# STM32F050F_Base.net
KiCad netlist of a schematic drawn in EAGLE
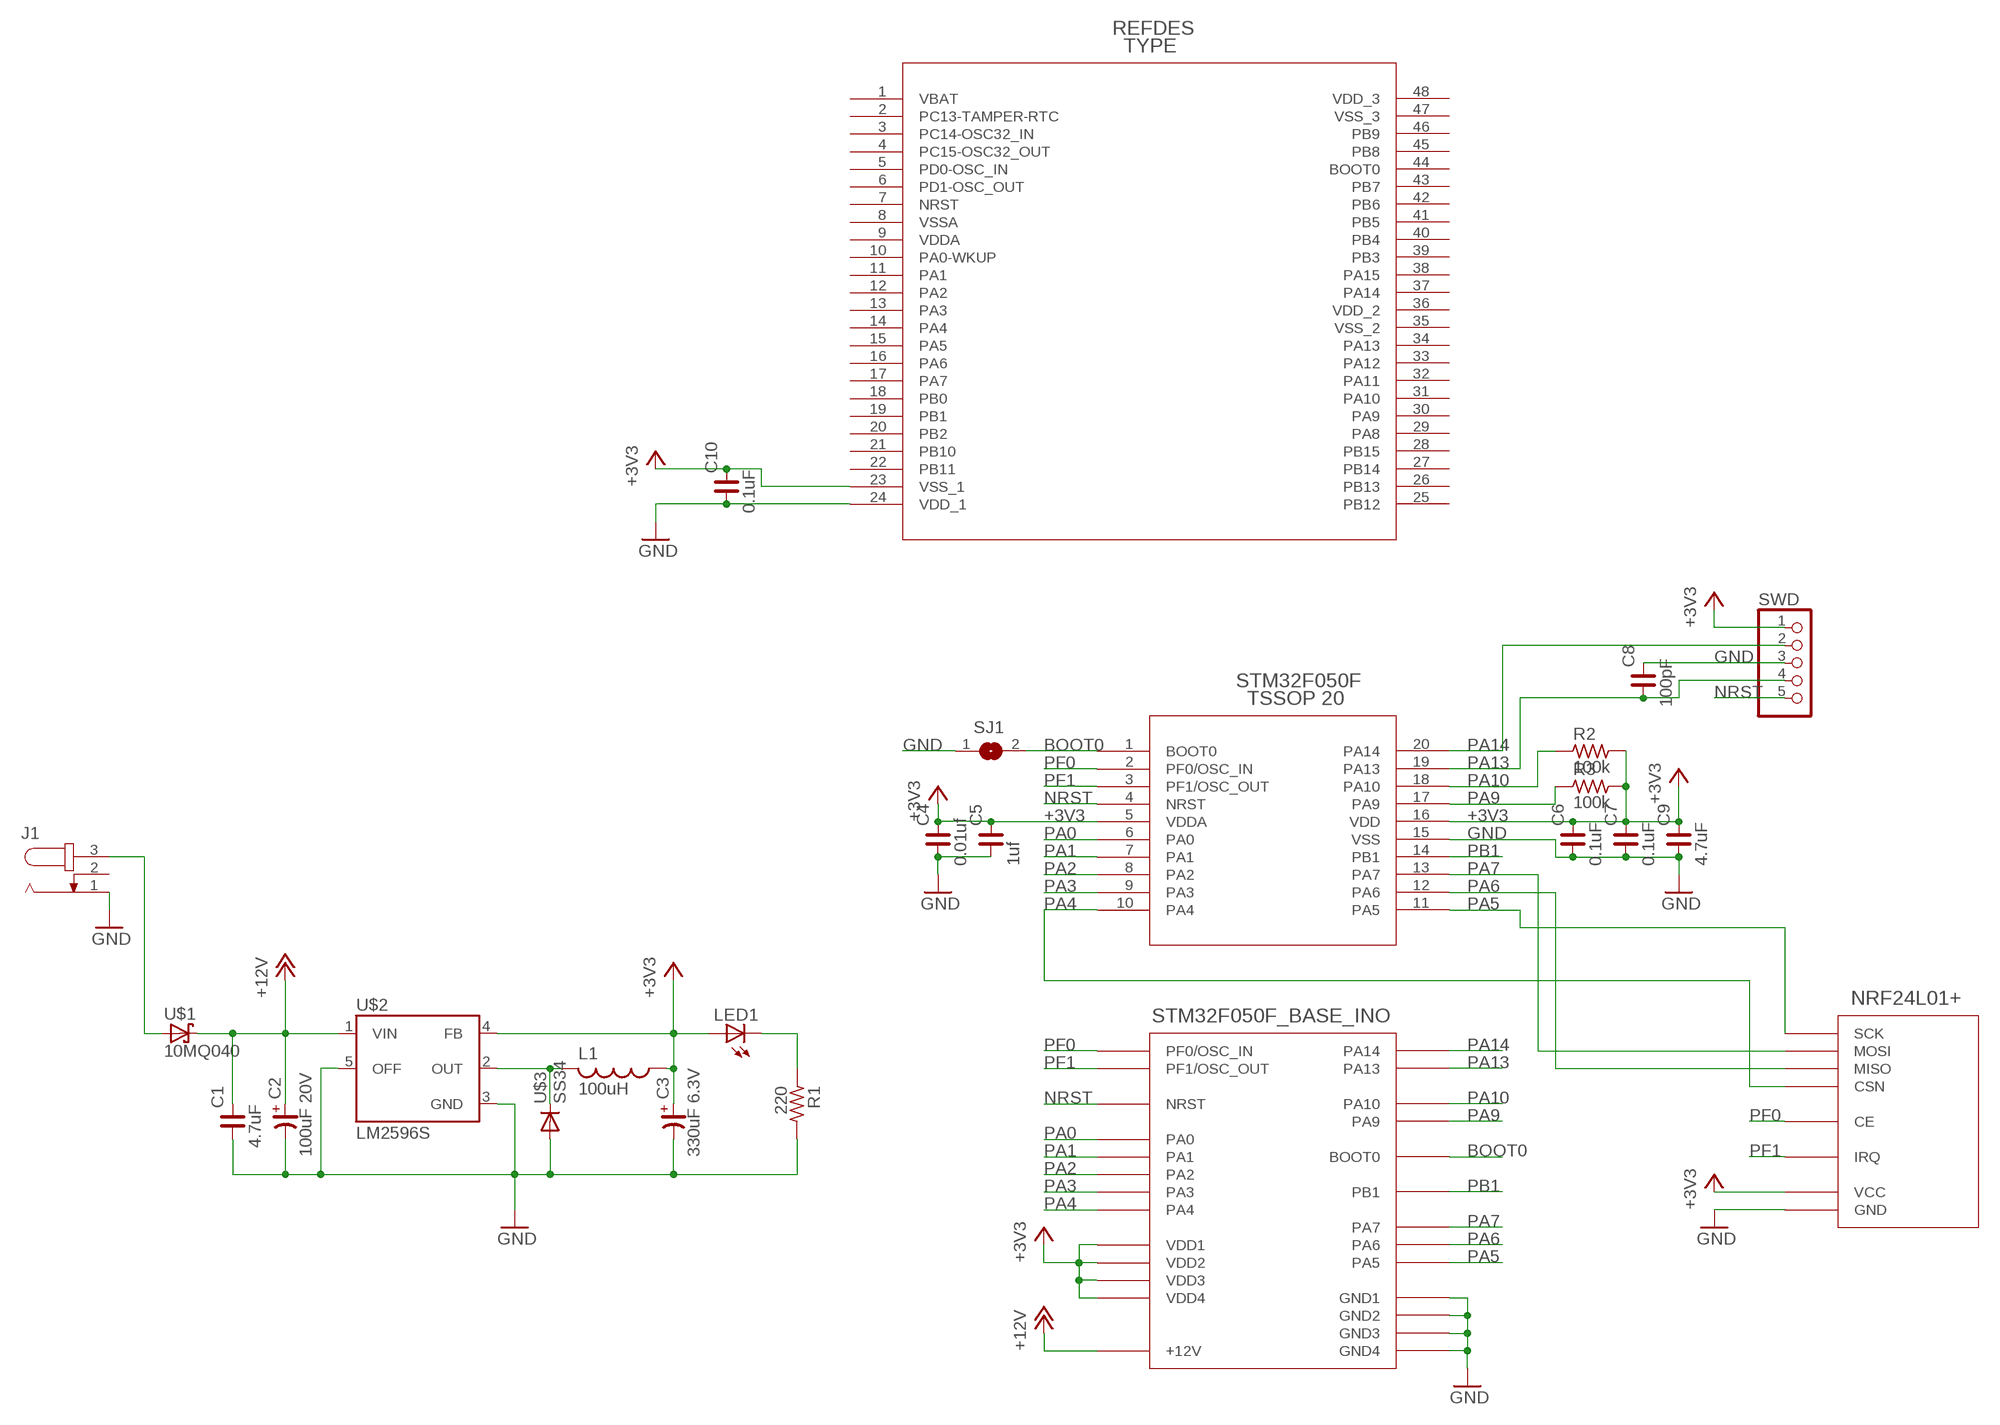
[diagram p0: schematic, sheet 1]

(export (version "E")
  (design (tool "Eeschema 10.0.6"))
  (components
    (comp (ref "C1")
      (value "4.7uF")
      (footprint "eagle-import:C1206")
      (libsource (lib "eagle-import") (part "C_1206"))
    )
    (comp (ref "C2")
      (value "100uF 20V")
      (footprint "eagle-import:C7343_T")
      (libsource (lib "eagle-import") (part "CP_7343"))
    )
    (comp (ref "C3")
      (value "330uF 6.3V")
      (footprint "eagle-import:C7343_T")
      (libsource (lib "eagle-import") (part "CP_7343"))
    )
    (comp (ref "C4")
      (value "0.01uf")
      (footprint "eagle-import:C1206")
      (libsource (lib "eagle-import") (part "C_1206"))
    )
    (comp (ref "C5")
      (value "1uf")
      (footprint "eagle-import:C1206")
      (libsource (lib "eagle-import") (part "C_1206"))
    )
    (comp (ref "C6")
      (value "0.1uF")
      (footprint "eagle-import:C1206")
      (libsource (lib "eagle-import") (part "C_1206"))
    )
    (comp (ref "C7")
      (value "0.1uF")
      (footprint "eagle-import:C1206")
      (libsource (lib "eagle-import") (part "C_1206"))
    )
    (comp (ref "C8")
      (value "100pF")
      (footprint "eagle-import:C1206")
      (libsource (lib "eagle-import") (part "C_1206"))
    )
    (comp (ref "C9")
      (value "4.7uF")
      (footprint "eagle-import:C1206")
      (libsource (lib "eagle-import") (part "C_1206"))
    )
    (comp (ref "C10")
      (value "0.1uF")
      (footprint "eagle-import:C1206")
      (libsource (lib "eagle-import") (part "C_1206"))
    )
    (comp (ref "J1")
      (value "JACK-PLUG0")
      (footprint "eagle-import:SPC4077")
      (libsource (lib "eagle-import") (part "JACK-PLUG0"))
    )
    (comp (ref "L1")
      (value "100uH")
      (footprint "eagle-import:POWER-CHOKE_WE-TPC")
      (libsource (lib "eagle-import") (part "L-USWE-TPC"))
    )
    (comp (ref "LED1")
      (value "LEDCHIPLED_1206")
      (footprint "eagle-import:CHIPLED_1206")
      (libsource (lib "eagle-import") (part "LEDCHIPLED_1206"))
    )
    (comp (ref "R1")
      (value "220")
      (footprint "eagle-import:R1206")
      (libsource (lib "eagle-import") (part "R_1206"))
    )
    (comp (ref "R2")
      (value "100k")
      (footprint "eagle-import:R1206")
      (libsource (lib "eagle-import") (part "R_1206"))
    )
    (comp (ref "R3")
      (value "100k")
      (footprint "eagle-import:R1206")
      (libsource (lib "eagle-import") (part "R_1206"))
    )
    (comp (ref "SJ1") (value "SJ") (footprint "eagle-import:SJ") (libsource (lib "eagle-import") (part "SJ")))
    (comp (ref "SWD")
      (value "PINHD-1X05_2.54-90°-S")
      (footprint "eagle-import:1X05_90-S")
      (libsource (lib "eagle-import") (part "PINHD-1X05_2.54-90°-S"))
    )
    (comp (ref "U$1")
      (value "10MQ040")
      (footprint "eagle-import:SMA")
      (libsource (lib "eagle-import") (part "10MQ040"))
    )
    (comp (ref "U$2")
      (value "LM2596S")
      (footprint "eagle-import:TO263-5")
      (libsource (lib "eagle-import") (part "LM2596S"))
    )
    (comp (ref "U$3")
      (value "SS34")
      (footprint "eagle-import:SMC")
      (libsource (lib "eagle-import") (part "DIODE-SMC"))
    )
    (comp (ref "U$4")
      (value "STM32F050F4P6")
      (footprint "eagle-import:TSSOP20")
      (libsource (lib "eagle-import") (part "STM32F050F4P6"))
    )
    (comp (ref "U$5")
      (value "STM32F050F_BASE_INO")
      (footprint "eagle-import:STM32_BASE_INO")
      (libsource (lib "eagle-import") (part "STM32F050F_BASE_INO"))
    )
    (comp (ref "U$6")
      (value "NRF24L01+")
      (footprint "eagle-import:NRF24L01+")
      (libsource (lib "eagle-import") (part "NRF24L01+"))
    )
    (comp (ref "U$7")
      (value "STM32F100C8T6B")
      (footprint "eagle-import:LQFP-48")
      (libsource (lib "eagle-import") (part "STM32F100C8T6B"))
    )
  )
  (nets
    (net (code "1") (name "+3V3") (class "Default")
      (node (ref "C10") (pin "2") (pinfunction "2_2") (pintype "passive"))
      (node (ref "C3") (pin "+") (pinfunction "+_+") (pintype "passive"))
      (node (ref "C4") (pin "2") (pinfunction "2_2") (pintype "passive"))
      (node (ref "C5") (pin "2") (pinfunction "2_2") (pintype "passive"))
      (node (ref "C6") (pin "2") (pinfunction "2_2") (pintype "passive"))
      (node (ref "C7") (pin "2") (pinfunction "2_2") (pintype "passive"))
      (node (ref "C9") (pin "2") (pinfunction "2_2") (pintype "passive"))
      (node (ref "L1") (pin "1") (pinfunction "1_1") (pintype "passive"))
      (node (ref "LED1") (pin "A") (pinfunction "A_A") (pintype "passive"))
      (node (ref "R2") (pin "2") (pinfunction "2_2") (pintype "passive"))
      (node (ref "R3") (pin "2") (pinfunction "2_2") (pintype "passive"))
      (node (ref "SWD") (pin "1") (pinfunction "1_1") (pintype "passive"))
      (node (ref "U$2") (pin "4") (pinfunction "FB_4") (pintype "input"))
      (node (ref "U$4") (pin "16") (pinfunction "VDD_16") (pintype "passive"))
      (node (ref "U$4") (pin "5") (pinfunction "VDDA_5") (pintype "passive"))
      (node (ref "U$5") (pin "VDD1") (pinfunction "VDD1_VDD1") (pintype "passive"))
      (node (ref "U$5") (pin "VDD2") (pinfunction "VDD2_VDD2") (pintype "passive"))
      (node (ref "U$5") (pin "VDD3") (pinfunction "VDD3_VDD3") (pintype "passive"))
      (node (ref "U$5") (pin "VDD4") (pinfunction "VDD4_VDD4") (pintype "passive"))
      (node (ref "U$6") (pin "VCC") (pinfunction "VCC_VCC") (pintype "passive"))
      (node (ref "U$7") (pin "23") (pinfunction "VSS_1_23") (pintype "passive"))
    )
    (net (code "2") (name "+12V") (class "Default")
      (node (ref "C1") (pin "2") (pinfunction "2_2") (pintype "passive"))
      (node (ref "C2") (pin "+") (pinfunction "+_+") (pintype "passive"))
      (node (ref "U$1") (pin "C") (pinfunction "C_C") (pintype "passive"))
      (node (ref "U$2") (pin "1") (pinfunction "VIN_1") (pintype "power_in"))
      (node (ref "U$5") (pin "+12V") (pinfunction "+12V_+12V") (pintype "passive"))
    )
    (net (code "3") (name "/BOOT0") (class "Default")
      (node (ref "SJ1") (pin "2") (pinfunction "2_2") (pintype "passive"))
      (node (ref "U$4") (pin "1") (pinfunction "BOOT0_1") (pintype "passive"))
      (node (ref "U$5") (pin "BOOT0") (pinfunction "BOOT0_BOOT0") (pintype "passive"))
    )
    (net (code "4") (name "/NRST") (class "Default")
      (node (ref "SWD") (pin "5") (pinfunction "5_5") (pintype "passive"))
      (node (ref "U$4") (pin "4") (pinfunction "NRST_4") (pintype "passive"))
      (node (ref "U$5") (pin "NRST") (pinfunction "NRST_NRST") (pintype "passive"))
    )
    (net (code "5") (name "/PA0") (class "Default")
      (node (ref "U$4") (pin "6") (pinfunction "PA0_6") (pintype "passive"))
      (node (ref "U$5") (pin "PA0") (pinfunction "PA0_PA0") (pintype "passive"))
    )
    (net (code "6") (name "/PA1") (class "Default")
      (node (ref "U$4") (pin "7") (pinfunction "PA1_7") (pintype "passive"))
      (node (ref "U$5") (pin "PA1") (pinfunction "PA1_PA1") (pintype "passive"))
    )
    (net (code "7") (name "/PA2") (class "Default")
      (node (ref "U$4") (pin "8") (pinfunction "PA2_8") (pintype "passive"))
      (node (ref "U$5") (pin "PA2") (pinfunction "PA2_PA2") (pintype "passive"))
    )
    (net (code "8") (name "/PA3") (class "Default")
      (node (ref "U$4") (pin "9") (pinfunction "PA3_9") (pintype "passive"))
      (node (ref "U$5") (pin "PA3") (pinfunction "PA3_PA3") (pintype "passive"))
    )
    (net (code "9") (name "/PA4") (class "Default")
      (node (ref "U$4") (pin "10") (pinfunction "PA4_10") (pintype "passive"))
      (node (ref "U$5") (pin "PA4") (pinfunction "PA4_PA4") (pintype "passive"))
      (node (ref "U$6") (pin "CSN") (pinfunction "CSN_CSN") (pintype "passive"))
    )
    (net (code "10") (name "/PA5") (class "Default")
      (node (ref "U$4") (pin "11") (pinfunction "PA5_11") (pintype "passive"))
      (node (ref "U$5") (pin "PA5") (pinfunction "PA5_PA5") (pintype "passive"))
      (node (ref "U$6") (pin "SCK") (pinfunction "SCK_SCK") (pintype "passive"))
    )
    (net (code "11") (name "/PA6") (class "Default")
      (node (ref "U$4") (pin "12") (pinfunction "PA6_12") (pintype "passive"))
      (node (ref "U$5") (pin "PA6") (pinfunction "PA6_PA6") (pintype "passive"))
      (node (ref "U$6") (pin "MISO") (pinfunction "MISO_MISO") (pintype "passive"))
    )
    (net (code "12") (name "/PA7") (class "Default")
      (node (ref "U$4") (pin "13") (pinfunction "PA7_13") (pintype "passive"))
      (node (ref "U$5") (pin "PA7") (pinfunction "PA7_PA7") (pintype "passive"))
      (node (ref "U$6") (pin "MOSI") (pinfunction "MOSI_MOSI") (pintype "passive"))
    )
    (net (code "13") (name "/PA9") (class "Default")
      (node (ref "R3") (pin "1") (pinfunction "1_1") (pintype "passive"))
      (node (ref "U$4") (pin "17") (pinfunction "PA9_17") (pintype "passive"))
      (node (ref "U$5") (pin "PA9") (pinfunction "PA9_PA9") (pintype "passive"))
    )
    (net (code "14") (name "/PA10") (class "Default")
      (node (ref "R2") (pin "1") (pinfunction "1_1") (pintype "passive"))
      (node (ref "U$4") (pin "18") (pinfunction "PA10_18") (pintype "passive"))
      (node (ref "U$5") (pin "PA10") (pinfunction "PA10_PA10") (pintype "passive"))
    )
    (net (code "15") (name "/PA13") (class "Default")
      (node (ref "C8") (pin "1") (pinfunction "1_1") (pintype "passive"))
      (node (ref "SWD") (pin "4") (pinfunction "4_4") (pintype "passive"))
      (node (ref "U$4") (pin "19") (pinfunction "PA13_19") (pintype "passive"))
      (node (ref "U$5") (pin "PA13") (pinfunction "PA13_PA13") (pintype "passive"))
    )
    (net (code "16") (name "/PA14") (class "Default")
      (node (ref "SWD") (pin "2") (pinfunction "2_2") (pintype "passive"))
      (node (ref "U$4") (pin "20") (pinfunction "PA14_20") (pintype "passive"))
      (node (ref "U$5") (pin "PA14") (pinfunction "PA14_PA14") (pintype "passive"))
    )
    (net (code "17") (name "/PB1") (class "Default")
      (node (ref "U$4") (pin "14") (pinfunction "PB1_14") (pintype "passive"))
      (node (ref "U$5") (pin "PB1") (pinfunction "PB1_PB1") (pintype "passive"))
    )
    (net (code "18") (name "/PF0") (class "Default")
      (node (ref "U$4") (pin "2") (pinfunction "PF0/OSC_IN_2") (pintype "passive"))
      (node (ref "U$5") (pin "PF0") (pinfunction "PF0/OSC_IN_PF0") (pintype "passive"))
      (node (ref "U$6") (pin "CE") (pinfunction "CE_CE") (pintype "passive"))
    )
    (net (code "19") (name "/PF1") (class "Default")
      (node (ref "U$4") (pin "3") (pinfunction "PF1/OSC_OUT_3") (pintype "passive"))
      (node (ref "U$5") (pin "PF1") (pinfunction "PF1/OSC_OUT_PF1") (pintype "passive"))
      (node (ref "U$6") (pin "IRQ") (pinfunction "IRQ_IRQ") (pintype "passive"))
    )
    (net (code "20") (name "GND") (class "Default")
      (node (ref "C1") (pin "1") (pinfunction "1_1") (pintype "passive"))
      (node (ref "C10") (pin "1") (pinfunction "1_1") (pintype "passive"))
      (node (ref "C2") (pin "-") (pinfunction "-_-") (pintype "passive"))
      (node (ref "C3") (pin "-") (pinfunction "-_-") (pintype "passive"))
      (node (ref "C4") (pin "1") (pinfunction "1_1") (pintype "passive"))
      (node (ref "C5") (pin "1") (pinfunction "1_1") (pintype "passive"))
      (node (ref "C6") (pin "1") (pinfunction "1_1") (pintype "passive"))
      (node (ref "C7") (pin "1") (pinfunction "1_1") (pintype "passive"))
      (node (ref "C8") (pin "2") (pinfunction "2_2") (pintype "passive"))
      (node (ref "C9") (pin "1") (pinfunction "1_1") (pintype "passive"))
      (node (ref "J1") (pin "1") (pinfunction "1_1") (pintype "passive"))
      (node (ref "R1") (pin "2") (pinfunction "2_2") (pintype "passive"))
      (node (ref "SJ1") (pin "1") (pinfunction "1_1") (pintype "passive"))
      (node (ref "SWD") (pin "3") (pinfunction "3_3") (pintype "passive"))
      (node (ref "U$2") (pin "3") (pinfunction "GND_3") (pintype "power_in"))
      (node (ref "U$2") (pin "5") (pinfunction "OFF_5") (pintype "input"))
      (node (ref "U$3") (pin "A") (pinfunction "A_A") (pintype "passive"))
      (node (ref "U$4") (pin "15") (pinfunction "VSS_15") (pintype "passive"))
      (node (ref "U$5") (pin "GND1") (pinfunction "GND1_GND1") (pintype "passive"))
      (node (ref "U$5") (pin "GND2") (pinfunction "GND2_GND2") (pintype "passive"))
      (node (ref "U$5") (pin "GND3") (pinfunction "GND3_GND3") (pintype "passive"))
      (node (ref "U$5") (pin "GND4") (pinfunction "GND4_GND4") (pintype "passive"))
      (node (ref "U$6") (pin "GND") (pinfunction "GND_GND") (pintype "passive"))
      (node (ref "U$7") (pin "24") (pinfunction "VDD_1_24") (pintype "passive"))
    )
    (net (code "21") (name "Net-(J1-Pad3)") (class "Default")
      (node (ref "J1") (pin "3") (pinfunction "3_3") (pintype "passive"))
      (node (ref "U$1") (pin "A") (pinfunction "A_A") (pintype "passive"))
    )
    (net (code "22") (name "Net-(LED1-PadC)") (class "Default")
      (node (ref "LED1") (pin "C") (pinfunction "C_C") (pintype "passive"))
      (node (ref "R1") (pin "1") (pinfunction "1_1") (pintype "passive"))
    )
    (net (code "23") (name "Net-(U$2-OUT)") (class "Default")
      (node (ref "L1") (pin "2") (pinfunction "2_2") (pintype "passive"))
      (node (ref "U$2") (pin "2") (pinfunction "OUT_2") (pintype "output"))
      (node (ref "U$3") (pin "C") (pinfunction "C_C") (pintype "passive"))
    )
    (net (code "24") (name "unconnected-(J1-Pad2)") (class "Default")
      (node (ref "J1") (pin "2") (pinfunction "2_2") (pintype "passive"))
    )
    (net (code "25") (name "unconnected-(U$7-BOOT0-Pad44)") (class "Default")
      (node (ref "U$7") (pin "44") (pinfunction "BOOT0_44") (pintype "passive"))
    )
    (net (code "26") (name "unconnected-(U$7-NRST-Pad7)") (class "Default")
      (node (ref "U$7") (pin "7") (pinfunction "NRST_7") (pintype "passive"))
    )
    (net (code "27") (name "unconnected-(U$7-PA0-WKUP-Pad10)") (class "Default")
      (node (ref "U$7") (pin "10") (pinfunction "PA0-WKUP_10") (pintype "passive"))
    )
    (net (code "28") (name "unconnected-(U$7-PA1-Pad11)") (class "Default")
      (node (ref "U$7") (pin "11") (pinfunction "PA1_11") (pintype "passive"))
    )
    (net (code "29") (name "unconnected-(U$7-PA2-Pad12)") (class "Default")
      (node (ref "U$7") (pin "12") (pinfunction "PA2_12") (pintype "passive"))
    )
    (net (code "30") (name "unconnected-(U$7-PA3-Pad13)") (class "Default")
      (node (ref "U$7") (pin "13") (pinfunction "PA3_13") (pintype "passive"))
    )
    (net (code "31") (name "unconnected-(U$7-PA4-Pad14)") (class "Default")
      (node (ref "U$7") (pin "14") (pinfunction "PA4_14") (pintype "passive"))
    )
    (net (code "32") (name "unconnected-(U$7-PA5-Pad15)") (class "Default")
      (node (ref "U$7") (pin "15") (pinfunction "PA5_15") (pintype "passive"))
    )
    (net (code "33") (name "unconnected-(U$7-PA6-Pad16)") (class "Default")
      (node (ref "U$7") (pin "16") (pinfunction "PA6_16") (pintype "passive"))
    )
    (net (code "34") (name "unconnected-(U$7-PA7-Pad17)") (class "Default")
      (node (ref "U$7") (pin "17") (pinfunction "PA7_17") (pintype "passive"))
    )
    (net (code "35") (name "unconnected-(U$7-PA8-Pad29)") (class "Default")
      (node (ref "U$7") (pin "29") (pinfunction "PA8_29") (pintype "passive"))
    )
    (net (code "36") (name "unconnected-(U$7-PA9-Pad30)") (class "Default")
      (node (ref "U$7") (pin "30") (pinfunction "PA9_30") (pintype "passive"))
    )
    (net (code "37") (name "unconnected-(U$7-PA10-Pad31)") (class "Default")
      (node (ref "U$7") (pin "31") (pinfunction "PA10_31") (pintype "passive"))
    )
    (net (code "38") (name "unconnected-(U$7-PA11-Pad32)") (class "Default")
      (node (ref "U$7") (pin "32") (pinfunction "PA11_32") (pintype "passive"))
    )
    (net (code "39") (name "unconnected-(U$7-PA12-Pad33)") (class "Default")
      (node (ref "U$7") (pin "33") (pinfunction "PA12_33") (pintype "passive"))
    )
    (net (code "40") (name "unconnected-(U$7-PA13-Pad34)") (class "Default")
      (node (ref "U$7") (pin "34") (pinfunction "PA13_34") (pintype "passive"))
    )
    (net (code "41") (name "unconnected-(U$7-PA14-Pad37)") (class "Default")
      (node (ref "U$7") (pin "37") (pinfunction "PA14_37") (pintype "passive"))
    )
    (net (code "42") (name "unconnected-(U$7-PA15-Pad38)") (class "Default")
      (node (ref "U$7") (pin "38") (pinfunction "PA15_38") (pintype "passive"))
    )
    (net (code "43") (name "unconnected-(U$7-PB0-Pad18)") (class "Default")
      (node (ref "U$7") (pin "18") (pinfunction "PB0_18") (pintype "passive"))
    )
    (net (code "44") (name "unconnected-(U$7-PB1-Pad19)") (class "Default")
      (node (ref "U$7") (pin "19") (pinfunction "PB1_19") (pintype "passive"))
    )
    (net (code "45") (name "unconnected-(U$7-PB2-Pad20)") (class "Default")
      (node (ref "U$7") (pin "20") (pinfunction "PB2_20") (pintype "passive"))
    )
    (net (code "46") (name "unconnected-(U$7-PB3-Pad39)") (class "Default")
      (node (ref "U$7") (pin "39") (pinfunction "PB3_39") (pintype "passive"))
    )
    (net (code "47") (name "unconnected-(U$7-PB4-Pad40)") (class "Default")
      (node (ref "U$7") (pin "40") (pinfunction "PB4_40") (pintype "passive"))
    )
    (net (code "48") (name "unconnected-(U$7-PB5-Pad41)") (class "Default")
      (node (ref "U$7") (pin "41") (pinfunction "PB5_41") (pintype "passive"))
    )
    (net (code "49") (name "unconnected-(U$7-PB6-Pad42)") (class "Default")
      (node (ref "U$7") (pin "42") (pinfunction "PB6_42") (pintype "passive"))
    )
    (net (code "50") (name "unconnected-(U$7-PB7-Pad43)") (class "Default")
      (node (ref "U$7") (pin "43") (pinfunction "PB7_43") (pintype "passive"))
    )
    (net (code "51") (name "unconnected-(U$7-PB8-Pad45)") (class "Default")
      (node (ref "U$7") (pin "45") (pinfunction "PB8_45") (pintype "passive"))
    )
    (net (code "52") (name "unconnected-(U$7-PB9-Pad46)") (class "Default")
      (node (ref "U$7") (pin "46") (pinfunction "PB9_46") (pintype "passive"))
    )
    (net (code "53") (name "unconnected-(U$7-PB10-Pad21)") (class "Default")
      (node (ref "U$7") (pin "21") (pinfunction "PB10_21") (pintype "passive"))
    )
    (net (code "54") (name "unconnected-(U$7-PB11-Pad22)") (class "Default")
      (node (ref "U$7") (pin "22") (pinfunction "PB11_22") (pintype "passive"))
    )
    (net (code "55") (name "unconnected-(U$7-PB12-Pad25)") (class "Default")
      (node (ref "U$7") (pin "25") (pinfunction "PB12_25") (pintype "passive"))
    )
    (net (code "56") (name "unconnected-(U$7-PB13-Pad26)") (class "Default")
      (node (ref "U$7") (pin "26") (pinfunction "PB13_26") (pintype "passive"))
    )
    (net (code "57") (name "unconnected-(U$7-PB14-Pad27)") (class "Default")
      (node (ref "U$7") (pin "27") (pinfunction "PB14_27") (pintype "passive"))
    )
    (net (code "58") (name "unconnected-(U$7-PB15-Pad28)") (class "Default")
      (node (ref "U$7") (pin "28") (pinfunction "PB15_28") (pintype "passive"))
    )
    (net (code "59") (name "unconnected-(U$7-PC13-TAMPER-RTC-Pad2)") (class "Default")
      (node (ref "U$7") (pin "2") (pinfunction "PC13-TAMPER-RTC_2") (pintype "passive"))
    )
    (net (code "60") (name "unconnected-(U$7-PC14-OSC32_IN-Pad3)") (class "Default")
      (node (ref "U$7") (pin "3") (pinfunction "PC14-OSC32_IN_3") (pintype "passive"))
    )
    (net (code "61") (name "unconnected-(U$7-PC15-OSC32_OUT-Pad4)") (class "Default")
      (node (ref "U$7") (pin "4") (pinfunction "PC15-OSC32_OUT_4") (pintype "passive"))
    )
    (net (code "62") (name "unconnected-(U$7-PD0-OSC_IN-Pad5)") (class "Default")
      (node (ref "U$7") (pin "5") (pinfunction "PD0-OSC_IN_5") (pintype "passive"))
    )
    (net (code "63") (name "unconnected-(U$7-PD1-OSC_OUT-Pad6)") (class "Default")
      (node (ref "U$7") (pin "6") (pinfunction "PD1-OSC_OUT_6") (pintype "passive"))
    )
    (net (code "64") (name "unconnected-(U$7-VBAT-Pad1)") (class "Default")
      (node (ref "U$7") (pin "1") (pinfunction "VBAT_1") (pintype "passive"))
    )
    (net (code "65") (name "unconnected-(U$7-VDDA-Pad9)") (class "Default")
      (node (ref "U$7") (pin "9") (pinfunction "VDDA_9") (pintype "passive"))
    )
    (net (code "66") (name "unconnected-(U$7-VDD_2-Pad36)") (class "Default")
      (node (ref "U$7") (pin "36") (pinfunction "VDD_2_36") (pintype "passive"))
    )
    (net (code "67") (name "unconnected-(U$7-VDD_3-Pad48)") (class "Default")
      (node (ref "U$7") (pin "48") (pinfunction "VDD_3_48") (pintype "passive"))
    )
    (net (code "68") (name "unconnected-(U$7-VSSA-Pad8)") (class "Default")
      (node (ref "U$7") (pin "8") (pinfunction "VSSA_8") (pintype "passive"))
    )
    (net (code "69") (name "unconnected-(U$7-VSS_2-Pad35)") (class "Default")
      (node (ref "U$7") (pin "35") (pinfunction "VSS_2_35") (pintype "passive"))
    )
    (net (code "70") (name "unconnected-(U$7-VSS_3-Pad47)") (class "Default")
      (node (ref "U$7") (pin "47") (pinfunction "VSS_3_47") (pintype "passive"))
    )
  )
)
